# ToolDoorController.net
KiCad netlist of a schematic drawn in Altium Designer
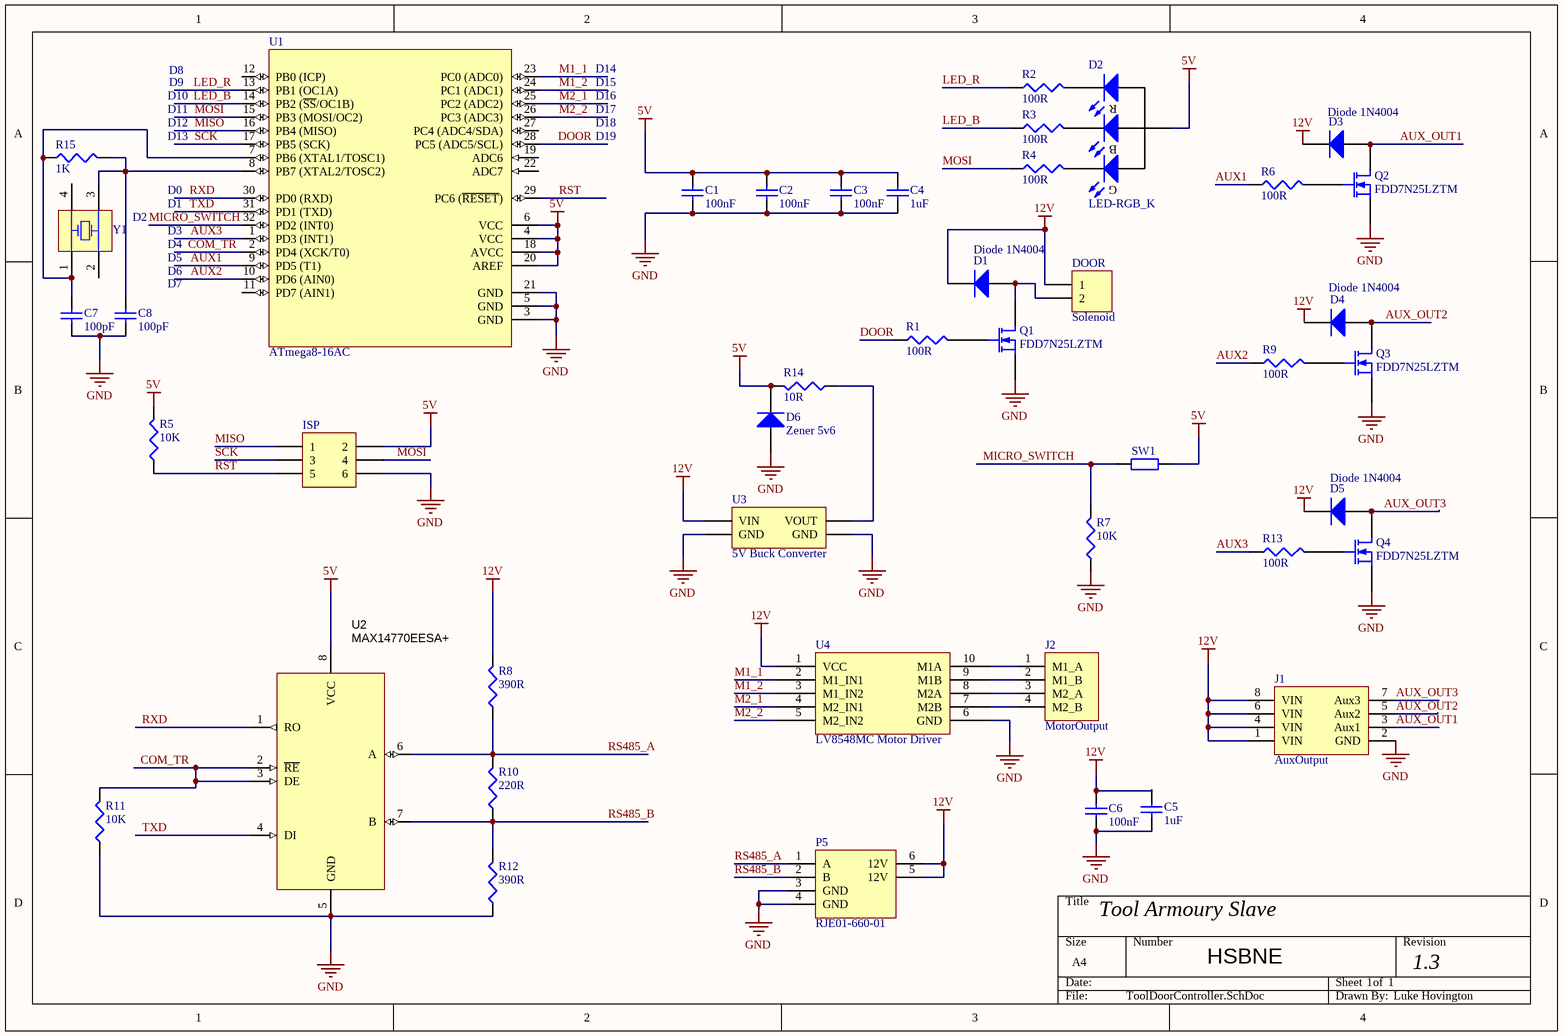
[diagram p0: ToolDoorController.SchDoc]

(export (version "E")
  (design (tool "Eeschema 10.0.6"))
  (components
    (comp (ref "C1")
      (value "100nF")
      (footprint "C1206")
      (description "Capacitor (Semiconductor SIM Model)")
      (fields (field (name "PUBLISHER") "Altium Limited"))
      (libsource (lib "ToolDoorController") (part "Cap 100nF"))
    )
    (comp (ref "C2")
      (value "100nF")
      (footprint "C1206")
      (description "Capacitor (Semiconductor SIM Model)")
      (fields (field (name "PUBLISHER") "Altium Limited"))
      (libsource (lib "ToolDoorController") (part "Cap 100nF"))
    )
    (comp (ref "C3")
      (value "100nF")
      (footprint "C1206")
      (description "Capacitor (Semiconductor SIM Model)")
      (fields (field (name "PUBLISHER") "Altium Limited"))
      (libsource (lib "ToolDoorController") (part "Cap 100nF"))
    )
    (comp (ref "C4")
      (value "1uF")
      (footprint "C1206")
      (description "Capacitor (Semiconductor SIM Model)")
      (fields (field (name "PUBLISHER") "Altium Limited"))
      (libsource (lib "ToolDoorController") (part "Cap 1uF"))
    )
    (comp (ref "C5")
      (value "1uF")
      (footprint "C1206")
      (description "Capacitor (Semiconductor SIM Model)")
      (fields (field (name "PUBLISHER") "Altium Limited"))
      (libsource (lib "ToolDoorController") (part "Cap 1uF"))
    )
    (comp (ref "C6")
      (value "100nF")
      (footprint "C1206")
      (description "Capacitor (Semiconductor SIM Model)")
      (fields (field (name "PUBLISHER") "Altium Limited"))
      (libsource (lib "ToolDoorController") (part "Cap 100nF"))
    )
    (comp (ref "C7")
      (value "100pF")
      (footprint "C1206")
      (description "Capacitor (Semiconductor SIM Model)")
      (fields (field (name "PUBLISHER") "Altium Limited"))
      (libsource (lib "ToolDoorController") (part "Cap 100nF"))
    )
    (comp (ref "C8")
      (value "100pF")
      (footprint "C1206")
      (description "Capacitor (Semiconductor SIM Model)")
      (fields (field (name "PUBLISHER") "Altium Limited"))
      (libsource (lib "ToolDoorController") (part "Cap 100nF"))
    )
    (comp (ref "D1")
      (value "Diode 1N4004")
      (footprint "DO-41")
      (description "1 Amp General Purpose Rectifier")
      (fields (field (name "PUBLISHER") "Altium Limited"))
      (libsource (lib "ToolDoorController") (part "Diode 1N4004"))
    )
    (comp (ref "D2")
      (value "LED-RGB_K")
      (footprint "RGB-CLVBAFKA")
      (description "RED, GREEN, BLUE LED")
      (fields (field (name "PUBLISHER") "Altium Limited"))
      (libsource (lib "ToolDoorController") (part "LED-RGB_K"))
    )
    (comp (ref "D3")
      (value "Diode 1N4004")
      (footprint "DO-41")
      (description "1 Amp General Purpose Rectifier")
      (fields (field (name "PUBLISHER") "Altium Limited"))
      (libsource (lib "ToolDoorController") (part "Diode 1N4004"))
    )
    (comp (ref "D4")
      (value "Diode 1N4004")
      (footprint "DO-41")
      (description "1 Amp General Purpose Rectifier")
      (fields (field (name "PUBLISHER") "Altium Limited"))
      (libsource (lib "ToolDoorController") (part "Diode 1N4004"))
    )
    (comp (ref "D5")
      (value "Diode 1N4004")
      (footprint "DO-41")
      (description "1 Amp General Purpose Rectifier")
      (fields (field (name "PUBLISHER") "Altium Limited"))
      (libsource (lib "ToolDoorController") (part "Diode 1N4004"))
    )
    (comp (ref "D6")
      (value "Zener 5v6")
      (footprint "DO-41")
      (description "5v6 Zener")
      (fields (field (name "PUBLISHER") "Altium Limited"))
      (libsource (lib "ToolDoorController") (part "Zener 1N5232BTR"))
    )
    (comp (ref "DOOR")
      (value "Solenoid")
      (footprint "JST-XH")
      (description "Header, 2-Pin")
      (fields (field (name "PUBLISHER") "Altium Limited"))
      (libsource (lib "ToolDoorController") (part "Header 2 JST-XH"))
    )
    (comp (ref "ISP")
      (value "ISP")
      (footprint "HDR2X3")
      (description "Header, 3-Pin, Dual row")
      (fields (field (name "PUBLISHER") "Altium Limited"))
      (libsource (lib "ToolDoorController") (part "Header 3X2"))
    )
    (comp (ref "J1")
      (value "AuxOutput")
      (footprint "AUX-Out")
      (description "AuxOut")
      (fields (field (name "PUBLISHER") "Altium Limited"))
      (libsource (lib "ToolDoorController") (part "AuxOut"))
    )
    (comp (ref "J2")
      (value "MotorOutput")
      (footprint "Motor_Out")
      (description "MotorOut")
      (fields (field (name "PUBLISHER") "Altium Limited"))
      (libsource (lib "ToolDoorController") (part "MotorOut"))
    )
    (comp (ref "P5")
      (value "RJE01-660-01")
      (footprint "RJ11")
      (description "RJ11")
      (libsource (lib "ToolDoorController") (part "RJ11"))
    )
    (comp (ref "Q1")
      (value "FDD7N25LZTM")
      (footprint "DPAC-3")
      (description "N-Channel MOSFET")
      (fields (field (name "PUBLISHER") "Altium Limited"))
      (libsource (lib "ToolDoorController") (part "MOSFET-N"))
    )
    (comp (ref "Q2")
      (value "FDD7N25LZTM")
      (footprint "DPAC-3")
      (description "N-Channel MOSFET")
      (fields (field (name "PUBLISHER") "Altium Limited"))
      (libsource (lib "ToolDoorController") (part "MOSFET-N"))
    )
    (comp (ref "Q3")
      (value "FDD7N25LZTM")
      (footprint "DPAC-3")
      (description "N-Channel MOSFET")
      (fields (field (name "PUBLISHER") "Altium Limited"))
      (libsource (lib "ToolDoorController") (part "MOSFET-N"))
    )
    (comp (ref "Q4")
      (value "FDD7N25LZTM")
      (footprint "DPAC-3")
      (description "N-Channel MOSFET")
      (fields (field (name "PUBLISHER") "Altium Limited"))
      (libsource (lib "ToolDoorController") (part "MOSFET-N"))
    )
    (comp (ref "R1")
      (value "100R")
      (footprint "C1206")
      (description "Resistor")
      (fields (field (name "PUBLISHER") "Altium Limited"))
      (libsource (lib "ToolDoorController") (part "Resistor-100R"))
    )
    (comp (ref "R2")
      (value "100R")
      (footprint "C1206")
      (description "Resistor")
      (fields (field (name "PUBLISHER") "Altium Limited"))
      (libsource (lib "ToolDoorController") (part "Resistor-100R"))
    )
    (comp (ref "R3")
      (value "100R")
      (footprint "C1206")
      (description "Resistor")
      (fields (field (name "PUBLISHER") "Altium Limited"))
      (libsource (lib "ToolDoorController") (part "Resistor-100R"))
    )
    (comp (ref "R4")
      (value "100R")
      (footprint "C1206")
      (description "Resistor")
      (fields (field (name "PUBLISHER") "Altium Limited"))
      (libsource (lib "ToolDoorController") (part "Resistor-100R"))
    )
    (comp (ref "R5")
      (value "10K")
      (footprint "C1206")
      (description "Resistor")
      (fields (field (name "PUBLISHER") "Altium Limited"))
      (libsource (lib "ToolDoorController") (part "Resistor-10K"))
    )
    (comp (ref "R6")
      (value "100R")
      (footprint "C1206")
      (description "Resistor")
      (fields (field (name "PUBLISHER") "Altium Limited"))
      (libsource (lib "ToolDoorController") (part "Resistor-100R"))
    )
    (comp (ref "R7")
      (value "10K")
      (footprint "C1206")
      (description "Resistor")
      (fields (field (name "PUBLISHER") "Altium Limited"))
      (libsource (lib "ToolDoorController") (part "Resistor-10K"))
    )
    (comp (ref "R8")
      (value "390R")
      (footprint "C1206")
      (description "Resistor")
      (fields (field (name "PUBLISHER") "Altium Limited"))
      (libsource (lib "ToolDoorController") (part "Resistor-390R"))
    )
    (comp (ref "R9")
      (value "100R")
      (footprint "C1206")
      (description "Resistor")
      (fields (field (name "PUBLISHER") "Altium Limited"))
      (libsource (lib "ToolDoorController") (part "Resistor-100R"))
    )
    (comp (ref "R10")
      (value "220R")
      (footprint "C1206")
      (description "Resistor")
      (fields (field (name "PUBLISHER") "Altium Limited"))
      (libsource (lib "ToolDoorController") (part "Resistor-220R"))
    )
    (comp (ref "R11")
      (value "10K")
      (footprint "C1206")
      (description "Resistor")
      (fields (field (name "PUBLISHER") "Altium Limited"))
      (libsource (lib "ToolDoorController") (part "Resistor-10K"))
    )
    (comp (ref "R12")
      (value "390R")
      (footprint "C1206")
      (description "Resistor")
      (fields (field (name "PUBLISHER") "Altium Limited"))
      (libsource (lib "ToolDoorController") (part "Resistor-390R"))
    )
    (comp (ref "R13")
      (value "100R")
      (footprint "C1206")
      (description "Resistor")
      (fields (field (name "PUBLISHER") "Altium Limited"))
      (libsource (lib "ToolDoorController") (part "Resistor-100R"))
    )
    (comp (ref "R14")
      (value "10R")
      (footprint "C1206")
      (description "Resistor")
      (fields (field (name "PUBLISHER") "Altium Limited"))
      (libsource (lib "ToolDoorController") (part "Resistor-10R"))
    )
    (comp (ref "R15")
      (value "1K")
      (footprint "C1206")
      (description "Resistor")
      (fields (field (name "PUBLISHER") "Altium Limited"))
      (libsource (lib "ToolDoorController") (part "Resistor-10K"))
    )
    (comp (ref "SW1")
      (value "Switch")
      (footprint "ReedSwitch")
      (description "ReedSwitch")
      (fields (field (name "PUBLISHER") "Altium Limited"))
      (libsource (lib "ToolDoorController") (part "Switch"))
    )
    (comp (ref "U1")
      (value "ATmega8-16AC")
      (footprint "32A_N")
      (description "8-Bit AVR Microcontroller with 8K Bytes of In-System Programmable Flash Memory")
      (fields (field (name "PUBLISHER") "Altium Limited"))
      (libsource (lib "ToolDoorController") (part "ATmega8-16AC"))
    )
    (comp (ref "U2")
      (value "MAX14770EESA+")
      (footprint "8S1_L")
      (description "TXRX PROFIBUS RS-485 8-SOIC")
      (libsource (lib "ToolDoorController") (part "MAX14770EESA+"))
    )
    (comp (ref "U3")
      (value "5V Buck Converter")
      (footprint "Buck_Module - upsidedown")
      (description "5V Buck Converter Module")
      (fields (field (name "PUBLISHER") "Altium Limited"))
      (libsource (lib "ToolDoorController") (part "5V Buck"))
    )
    (comp (ref "U4")
      (value "LV8548MC Motor Driver")
      (footprint "10S1_M")
      (description "Forward/Reverse Motor Driver")
      (libsource (lib "ToolDoorController") (part "LV8548MC"))
    )
    (comp (ref "Y1")
      (value "Crystal")
      (footprint "CRYSTAL_AXIAL")
      (description "Surface Mount Quartz Crystal")
      (fields (field (name "PUBLISHER") "Altium Limited"))
      (libsource (lib "ToolDoorController") (part "Crystal"))
    )
  )
  (nets
    (net (code "1") (name "/AUX1") (class "Default")
      (node (ref "R6") (pin "1") (pinfunction "1_1") (pintype "passive"))
      (node (ref "U1") (pin "9") (pinfunction "PD5_(T1)_9") (pintype "bidirectional"))
    )
    (net (code "2") (name "/AUX2") (class "Default")
      (node (ref "R9") (pin "1") (pinfunction "1_1") (pintype "passive"))
      (node (ref "U1") (pin "10") (pinfunction "PD6_(AIN0)_10") (pintype "bidirectional"))
    )
    (net (code "3") (name "/AUX3") (class "Default")
      (node (ref "R13") (pin "1") (pinfunction "1_1") (pintype "passive"))
      (node (ref "U1") (pin "1") (pinfunction "PD3_(INT1)_1") (pintype "bidirectional"))
    )
    (net (code "4") (name "/AUX_OUT1") (class "Default")
      (node (ref "D3") (pin "1") (pinfunction "A_1") (pintype "passive"))
      (node (ref "J1") (pin "3") (pinfunction "Aux1_3") (pintype "passive"))
      (node (ref "Q2") (pin "1") (pinfunction "D_1") (pintype "passive"))
    )
    (net (code "5") (name "/AUX_OUT2") (class "Default")
      (node (ref "D4") (pin "1") (pinfunction "A_1") (pintype "passive"))
      (node (ref "J1") (pin "5") (pinfunction "Aux2_5") (pintype "passive"))
      (node (ref "Q3") (pin "1") (pinfunction "D_1") (pintype "passive"))
    )
    (net (code "6") (name "/AUX_OUT3") (class "Default")
      (node (ref "D5") (pin "1") (pinfunction "A_1") (pintype "passive"))
      (node (ref "J1") (pin "7") (pinfunction "Aux3_7") (pintype "passive"))
      (node (ref "Q4") (pin "1") (pinfunction "D_1") (pintype "passive"))
    )
    (net (code "7") (name "/COM_TR") (class "Default")
      (node (ref "R11") (pin "2") (pinfunction "2_2") (pintype "passive"))
      (node (ref "U1") (pin "2") (pinfunction "PD4_(XCK/T0)_2") (pintype "bidirectional"))
      (node (ref "U2") (pin "2") (pinfunction "~{RE}_2") (pintype "input"))
      (node (ref "U2") (pin "3") (pinfunction "DE_3") (pintype "input"))
    )
    (net (code "8") (name "/DOOR") (class "Default")
      (node (ref "R1") (pin "1") (pinfunction "1_1") (pintype "passive"))
      (node (ref "U1") (pin "28") (pinfunction "PC5_(ADC5/SCL)_28") (pintype "bidirectional"))
    )
    (net (code "9") (name "/LED_B") (class "Default")
      (node (ref "R3") (pin "1") (pinfunction "1_1") (pintype "passive"))
      (node (ref "U1") (pin "14") (pinfunction "PB2_(~{SS}/OC1B)_14") (pintype "bidirectional"))
    )
    (net (code "10") (name "/LED_R") (class "Default")
      (node (ref "R2") (pin "1") (pinfunction "1_1") (pintype "passive"))
      (node (ref "U1") (pin "13") (pinfunction "PB1_(OC1A)_13") (pintype "bidirectional"))
    )
    (net (code "11") (name "/M1_1") (class "Default")
      (node (ref "U1") (pin "23") (pinfunction "PC0_(ADC0)_23") (pintype "bidirectional"))
      (node (ref "U4") (pin "2") (pinfunction "M1_IN1_2") (pintype "passive"))
    )
    (net (code "12") (name "/M1_2") (class "Default")
      (node (ref "U1") (pin "24") (pinfunction "PC1_(ADC1)_24") (pintype "bidirectional"))
      (node (ref "U4") (pin "3") (pinfunction "M1_IN2_3") (pintype "passive"))
    )
    (net (code "13") (name "/M2_1") (class "Default")
      (node (ref "U1") (pin "25") (pinfunction "PC2_(ADC2)_25") (pintype "bidirectional"))
      (node (ref "U4") (pin "4") (pinfunction "M2_IN1_4") (pintype "passive"))
    )
    (net (code "14") (name "/M2_2") (class "Default")
      (node (ref "U1") (pin "26") (pinfunction "PC3_(ADC3)_26") (pintype "bidirectional"))
      (node (ref "U4") (pin "5") (pinfunction "M2_IN2_5") (pintype "passive"))
    )
    (net (code "15") (name "/MICRO_SWITCH") (class "Default")
      (node (ref "R7") (pin "2") (pinfunction "2_2") (pintype "passive"))
      (node (ref "SW1") (pin "1") (pinfunction "1_1") (pintype "passive"))
      (node (ref "U1") (pin "32") (pinfunction "PD2_(INT0)_32") (pintype "bidirectional"))
    )
    (net (code "16") (name "/MISO") (class "Default")
      (node (ref "ISP") (pin "1") (pinfunction "1_1") (pintype "passive"))
      (node (ref "U1") (pin "16") (pinfunction "PB4_(MISO)_16") (pintype "bidirectional"))
    )
    (net (code "17") (name "/MOSI") (class "Default")
      (node (ref "ISP") (pin "4") (pinfunction "4_4") (pintype "passive"))
      (node (ref "R4") (pin "1") (pinfunction "1_1") (pintype "passive"))
      (node (ref "U1") (pin "15") (pinfunction "PB3_(MOSI/OC2)_15") (pintype "bidirectional"))
    )
    (net (code "18") (name "/RS485_A") (class "Default")
      (node (ref "P5") (pin "1") (pinfunction "A_1") (pintype "passive"))
      (node (ref "R10") (pin "2") (pinfunction "2_2") (pintype "passive"))
      (node (ref "R8") (pin "1") (pinfunction "1_1") (pintype "passive"))
      (node (ref "U2") (pin "6") (pinfunction "A_6") (pintype "bidirectional"))
    )
    (net (code "19") (name "/RS485_B") (class "Default")
      (node (ref "P5") (pin "2") (pinfunction "B_2") (pintype "passive"))
      (node (ref "R10") (pin "1") (pinfunction "1_1") (pintype "passive"))
      (node (ref "R12") (pin "2") (pinfunction "2_2") (pintype "passive"))
      (node (ref "U2") (pin "7") (pinfunction "B_7") (pintype "bidirectional"))
    )
    (net (code "20") (name "/RST") (class "Default")
      (node (ref "ISP") (pin "5") (pinfunction "5_5") (pintype "passive"))
      (node (ref "R5") (pin "1") (pinfunction "1_1") (pintype "passive"))
      (node (ref "U1") (pin "29") (pinfunction "PC6_(~{RESET})_29") (pintype "bidirectional"))
    )
    (net (code "21") (name "/RXD") (class "Default")
      (node (ref "U1") (pin "30") (pinfunction "PD0_(RXD)_30") (pintype "bidirectional"))
      (node (ref "U2") (pin "1") (pinfunction "RO_1") (pintype "output"))
    )
    (net (code "22") (name "/SCK") (class "Default")
      (node (ref "ISP") (pin "3") (pinfunction "3_3") (pintype "passive"))
      (node (ref "U1") (pin "17") (pinfunction "PB5_(SCK)_17") (pintype "bidirectional"))
    )
    (net (code "23") (name "/TXD") (class "Default")
      (node (ref "U1") (pin "31") (pinfunction "PD1_(TXD)_31") (pintype "bidirectional"))
      (node (ref "U2") (pin "4") (pinfunction "DI_4") (pintype "input"))
    )
    (net (code "24") (name "5V") (class "Default")
      (node (ref "C1") (pin "2") (pinfunction "2_2") (pintype "passive"))
      (node (ref "C2") (pin "2") (pinfunction "2_2") (pintype "passive"))
      (node (ref "C3") (pin "2") (pinfunction "2_2") (pintype "passive"))
      (node (ref "C4") (pin "2") (pinfunction "2_2") (pintype "passive"))
      (node (ref "D2") (pin "2") (pinfunction "A_2") (pintype "passive"))
      (node (ref "D6") (pin "2") (pinfunction "K_2") (pintype "passive"))
      (node (ref "ISP") (pin "2") (pinfunction "2_2") (pintype "passive"))
      (node (ref "R14") (pin "2") (pinfunction "2_2") (pintype "passive"))
      (node (ref "R5") (pin "2") (pinfunction "2_2") (pintype "passive"))
      (node (ref "SW1") (pin "2") (pinfunction "2_2") (pintype "passive"))
      (node (ref "U1") (pin "18") (pinfunction "AVCC_18") (pintype "power_in"))
      (node (ref "U1") (pin "20") (pinfunction "AREF_20") (pintype "passive"))
      (node (ref "U1") (pin "4") (pinfunction "VCC_4") (pintype "power_in"))
      (node (ref "U1") (pin "6") (pinfunction "VCC_6") (pintype "power_in"))
      (node (ref "U2") (pin "8") (pinfunction "VCC_8") (pintype "power_in"))
    )
    (net (code "25") (name "12V") (class "Default")
      (node (ref "C5") (pin "2") (pinfunction "2_2") (pintype "passive"))
      (node (ref "C6") (pin "2") (pinfunction "2_2") (pintype "passive"))
      (node (ref "D1") (pin "2") (pinfunction "K_2") (pintype "passive"))
      (node (ref "D3") (pin "2") (pinfunction "K_2") (pintype "passive"))
      (node (ref "D4") (pin "2") (pinfunction "K_2") (pintype "passive"))
      (node (ref "D5") (pin "2") (pinfunction "K_2") (pintype "passive"))
      (node (ref "DOOR") (pin "1") (pinfunction "1_1") (pintype "passive"))
      (node (ref "J1") (pin "1") (pinfunction "VIN_1") (pintype "passive"))
      (node (ref "J1") (pin "4") (pinfunction "VIN_4") (pintype "passive"))
      (node (ref "J1") (pin "6") (pinfunction "VIN_6") (pintype "passive"))
      (node (ref "J1") (pin "8") (pinfunction "VIN_8") (pintype "passive"))
      (node (ref "P5") (pin "5") (pinfunction "12V_5") (pintype "passive"))
      (node (ref "P5") (pin "6") (pinfunction "12V_6") (pintype "passive"))
      (node (ref "R8") (pin "2") (pinfunction "2_2") (pintype "passive"))
      (node (ref "U3") (pin "1") (pinfunction "VIN_1") (pintype "passive"))
      (node (ref "U4") (pin "1") (pinfunction "VCC_1") (pintype "passive"))
    )
    (net (code "26") (name "GND") (class "Default")
      (node (ref "C1") (pin "1") (pinfunction "1_1") (pintype "passive"))
      (node (ref "C2") (pin "1") (pinfunction "1_1") (pintype "passive"))
      (node (ref "C3") (pin "1") (pinfunction "1_1") (pintype "passive"))
      (node (ref "C4") (pin "1") (pinfunction "1_1") (pintype "passive"))
      (node (ref "C5") (pin "1") (pinfunction "1_1") (pintype "passive"))
      (node (ref "C6") (pin "1") (pinfunction "1_1") (pintype "passive"))
      (node (ref "C7") (pin "1") (pinfunction "1_1") (pintype "passive"))
      (node (ref "C8") (pin "1") (pinfunction "1_1") (pintype "passive"))
      (node (ref "D6") (pin "1") (pinfunction "A_1") (pintype "passive"))
      (node (ref "ISP") (pin "6") (pinfunction "6_6") (pintype "passive"))
      (node (ref "J1") (pin "2") (pinfunction "GND_2") (pintype "passive"))
      (node (ref "P5") (pin "3") (pinfunction "GND_3") (pintype "passive"))
      (node (ref "P5") (pin "4") (pinfunction "GND_4") (pintype "passive"))
      (node (ref "Q1") (pin "3") (pinfunction "S_3") (pintype "passive"))
      (node (ref "Q2") (pin "3") (pinfunction "S_3") (pintype "passive"))
      (node (ref "Q3") (pin "3") (pinfunction "S_3") (pintype "passive"))
      (node (ref "Q4") (pin "3") (pinfunction "S_3") (pintype "passive"))
      (node (ref "R11") (pin "1") (pinfunction "1_1") (pintype "passive"))
      (node (ref "R12") (pin "1") (pinfunction "1_1") (pintype "passive"))
      (node (ref "R7") (pin "1") (pinfunction "1_1") (pintype "passive"))
      (node (ref "U1") (pin "21") (pinfunction "GND_21") (pintype "power_in"))
      (node (ref "U1") (pin "3") (pinfunction "GND_3") (pintype "power_in"))
      (node (ref "U1") (pin "5") (pinfunction "GND_5") (pintype "power_in"))
      (node (ref "U2") (pin "5") (pinfunction "GND_5") (pintype "power_in"))
      (node (ref "U3") (pin "3") (pinfunction "GND_3") (pintype "passive"))
      (node (ref "U3") (pin "4") (pinfunction "GND_4") (pintype "passive"))
      (node (ref "U4") (pin "6") (pinfunction "GND_6") (pintype "passive"))
    )
    (net (code "27") (name "Net-(D1-A)") (class "Default")
      (node (ref "D1") (pin "1") (pinfunction "A_1") (pintype "passive"))
      (node (ref "DOOR") (pin "2") (pinfunction "2_2") (pintype "passive"))
      (node (ref "Q1") (pin "1") (pinfunction "D_1") (pintype "passive"))
    )
    (net (code "28") (name "Net-(D2-K-B)") (class "Default")
      (node (ref "D2") (pin "3") (pinfunction "K-B_3") (pintype "passive"))
      (node (ref "R3") (pin "2") (pinfunction "2_2") (pintype "passive"))
    )
    (net (code "29") (name "Net-(D2-K-G)") (class "Default")
      (node (ref "D2") (pin "4") (pinfunction "K-G_4") (pintype "passive"))
      (node (ref "R4") (pin "2") (pinfunction "2_2") (pintype "passive"))
    )
    (net (code "30") (name "Net-(D2-K-R)") (class "Default")
      (node (ref "D2") (pin "1") (pinfunction "K-R_1") (pintype "passive"))
      (node (ref "R2") (pin "2") (pinfunction "2_2") (pintype "passive"))
    )
    (net (code "31") (name "Net-(J2-M1_A)") (class "Default")
      (node (ref "J2") (pin "1") (pinfunction "M1_A_1") (pintype "passive"))
      (node (ref "U4") (pin "10") (pinfunction "M1A_10") (pintype "passive"))
    )
    (net (code "32") (name "Net-(J2-M1_B)") (class "Default")
      (node (ref "J2") (pin "2") (pinfunction "M1_B_2") (pintype "passive"))
      (node (ref "U4") (pin "9") (pinfunction "M1B_9") (pintype "passive"))
    )
    (net (code "33") (name "Net-(J2-M2_A)") (class "Default")
      (node (ref "J2") (pin "3") (pinfunction "M2_A_3") (pintype "passive"))
      (node (ref "U4") (pin "8") (pinfunction "M2A_8") (pintype "passive"))
    )
    (net (code "34") (name "Net-(J2-M2_B)") (class "Default")
      (node (ref "J2") (pin "4") (pinfunction "M2_B_4") (pintype "passive"))
      (node (ref "U4") (pin "7") (pinfunction "M2B_7") (pintype "passive"))
    )
    (net (code "35") (name "Net-(Q1-G)") (class "Default")
      (node (ref "Q1") (pin "2") (pinfunction "G_2") (pintype "passive"))
      (node (ref "R1") (pin "2") (pinfunction "2_2") (pintype "passive"))
    )
    (net (code "36") (name "Net-(Q2-G)") (class "Default")
      (node (ref "Q2") (pin "2") (pinfunction "G_2") (pintype "passive"))
      (node (ref "R6") (pin "2") (pinfunction "2_2") (pintype "passive"))
    )
    (net (code "37") (name "Net-(Q3-G)") (class "Default")
      (node (ref "Q3") (pin "2") (pinfunction "G_2") (pintype "passive"))
      (node (ref "R9") (pin "2") (pinfunction "2_2") (pintype "passive"))
    )
    (net (code "38") (name "Net-(Q4-G)") (class "Default")
      (node (ref "Q4") (pin "2") (pinfunction "G_2") (pintype "passive"))
      (node (ref "R13") (pin "2") (pinfunction "2_2") (pintype "passive"))
    )
    (net (code "39") (name "Net-(U1-PB6_(XTAL1{slash}TOSC1))") (class "Default")
      (node (ref "C7") (pin "2") (pinfunction "2_2") (pintype "passive"))
      (node (ref "R15") (pin "1") (pinfunction "1_1") (pintype "passive"))
      (node (ref "U1") (pin "7") (pinfunction "PB6_(XTAL1/TOSC1)_7") (pintype "bidirectional"))
      (node (ref "Y1") (pin "1") (pinfunction "OSC1_1") (pintype "passive"))
    )
    (net (code "40") (name "Net-(U1-PB7_(XTAL2{slash}TOSC2))") (class "Default")
      (node (ref "C8") (pin "2") (pinfunction "2_2") (pintype "passive"))
      (node (ref "R15") (pin "2") (pinfunction "2_2") (pintype "passive"))
      (node (ref "U1") (pin "8") (pinfunction "PB7_(XTAL2/TOSC2)_8") (pintype "bidirectional"))
      (node (ref "Y1") (pin "3") (pinfunction "OSC2_3") (pintype "passive"))
    )
    (net (code "41") (name "Net-(U3-VOUT)") (class "Default")
      (node (ref "R14") (pin "1") (pinfunction "1_1") (pintype "passive"))
      (node (ref "U3") (pin "2") (pinfunction "VOUT_2") (pintype "passive"))
    )
    (net (code "42") (name "unconnected-(U1-ADC6-Pad19)") (class "Default")
      (node (ref "U1") (pin "19") (pinfunction "ADC6_19") (pintype "input"))
    )
    (net (code "43") (name "unconnected-(U1-ADC7-Pad22)") (class "Default")
      (node (ref "U1") (pin "22") (pinfunction "ADC7_22") (pintype "input"))
    )
    (net (code "44") (name "unconnected-(U1-PB0_(ICP)-Pad12)") (class "Default")
      (node (ref "U1") (pin "12") (pinfunction "PB0_(ICP)_12") (pintype "bidirectional"))
    )
    (net (code "45") (name "unconnected-(U1-PC4_(ADC4{slash}SDA)-Pad27)") (class "Default")
      (node (ref "U1") (pin "27") (pinfunction "PC4_(ADC4/SDA)_27") (pintype "bidirectional"))
    )
    (net (code "46") (name "unconnected-(U1-PD7_(AIN1)-Pad11)") (class "Default")
      (node (ref "U1") (pin "11") (pinfunction "PD7_(AIN1)_11") (pintype "bidirectional"))
    )
    (net (code "47") (name "unconnected-(Y1-OSC1-Pad4)") (class "Default")
      (node (ref "Y1") (pin "4") (pinfunction "OSC1_4") (pintype "passive"))
    )
    (net (code "48") (name "unconnected-(Y1-OSC2-Pad2)") (class "Default")
      (node (ref "Y1") (pin "2") (pinfunction "OSC2_2") (pintype "passive"))
    )
  )
)
